# TP_IHM_MAIN.net
KiCad netlist of a schematic drawn in Altium Designer
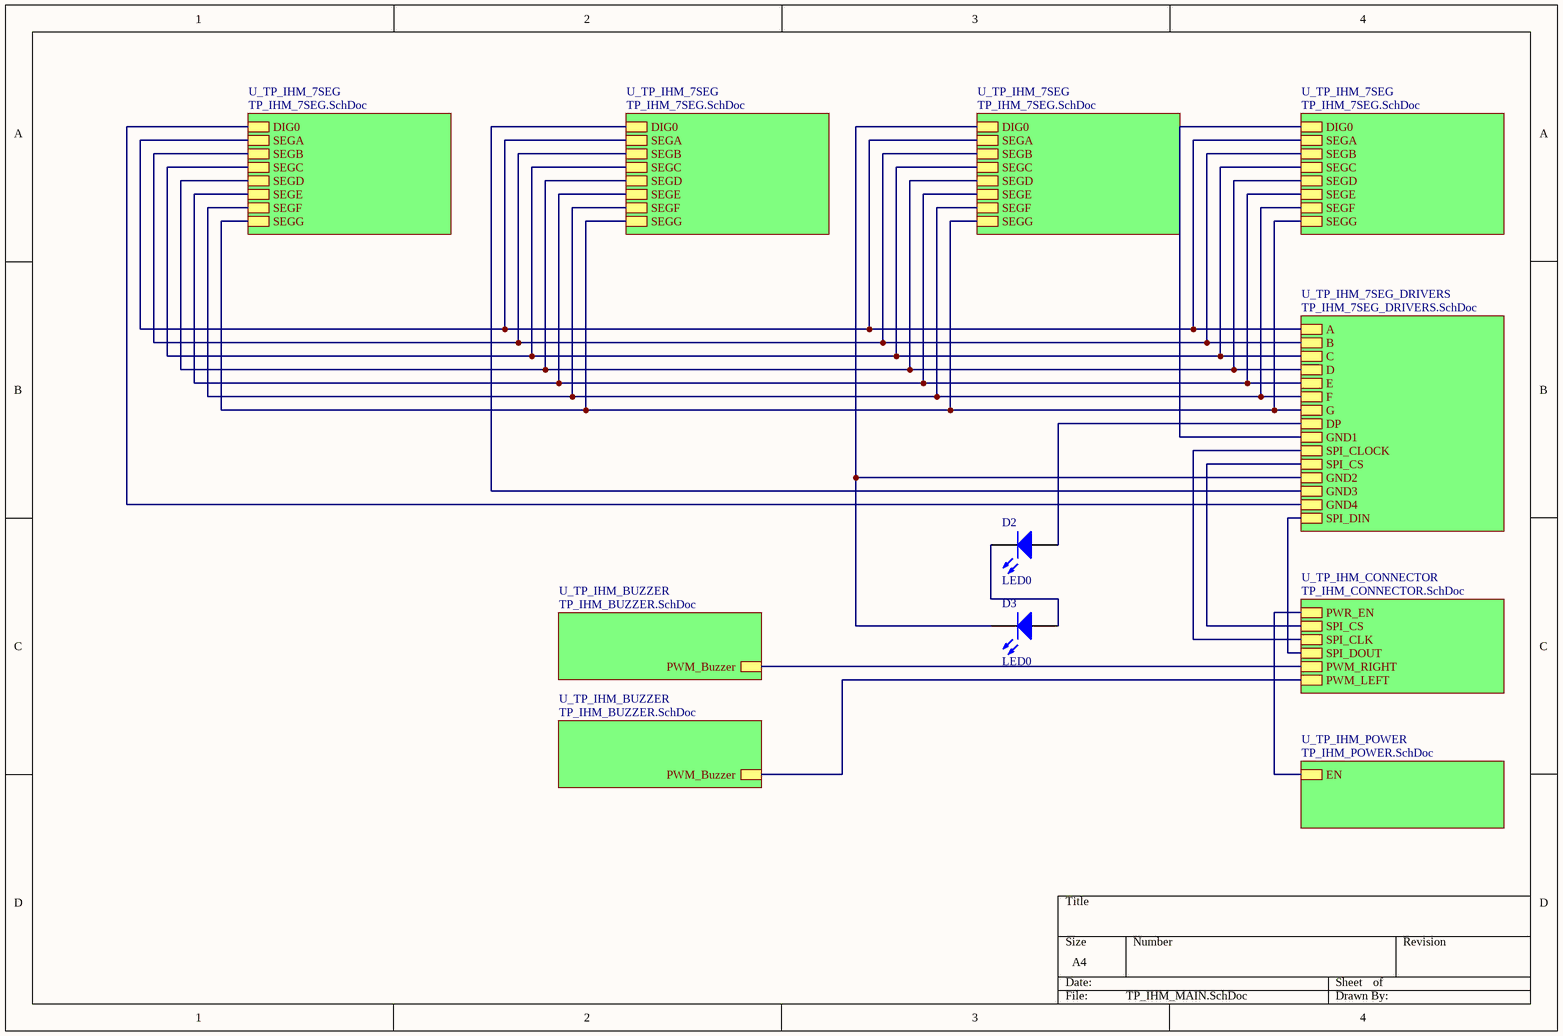
[diagram p0: TP_IHM_MAIN.SchDoc]

(export (version "E")
  (design (tool "Eeschema 10.0.6"))
  (components
    (comp (ref "D2")
      (value "LED0")
      (footprint "LED-0")
      (description "Typical INFRARED GaAs LED")
      (fields (field (name "PUBLISHER") "Altium Limited"))
      (libsource (lib "Miscellaneous Devices") (part "LED0"))
    )
    (comp (ref "D3")
      (value "LED0")
      (footprint "LED-0")
      (description "Typical INFRARED GaAs LED")
      (fields (field (name "PUBLISHER") "Altium Limited"))
      (libsource (lib "Miscellaneous Devices") (part "LED0"))
    )
  )
  (nets
    (net (code "6") (name "/DIG0_1") (class "Default")
      (node (ref "D3") (pin "2") (pinfunction "K_2") (pintype "passive"))
    )
    (net (code "9") (name "/DP") (class "Default")
      (node (ref "D2") (pin "1") (pinfunction "A_1") (pintype "passive"))
    )
    (net (code "19") (name "Net-(D2-K)") (class "Default")
      (node (ref "D2") (pin "2") (pinfunction "K_2") (pintype "passive"))
      (node (ref "D3") (pin "1") (pinfunction "A_1") (pintype "passive"))
    )
  )
)
